# BusPirate-v5.net
KiCad netlist of a schematic drawn in EAGLE
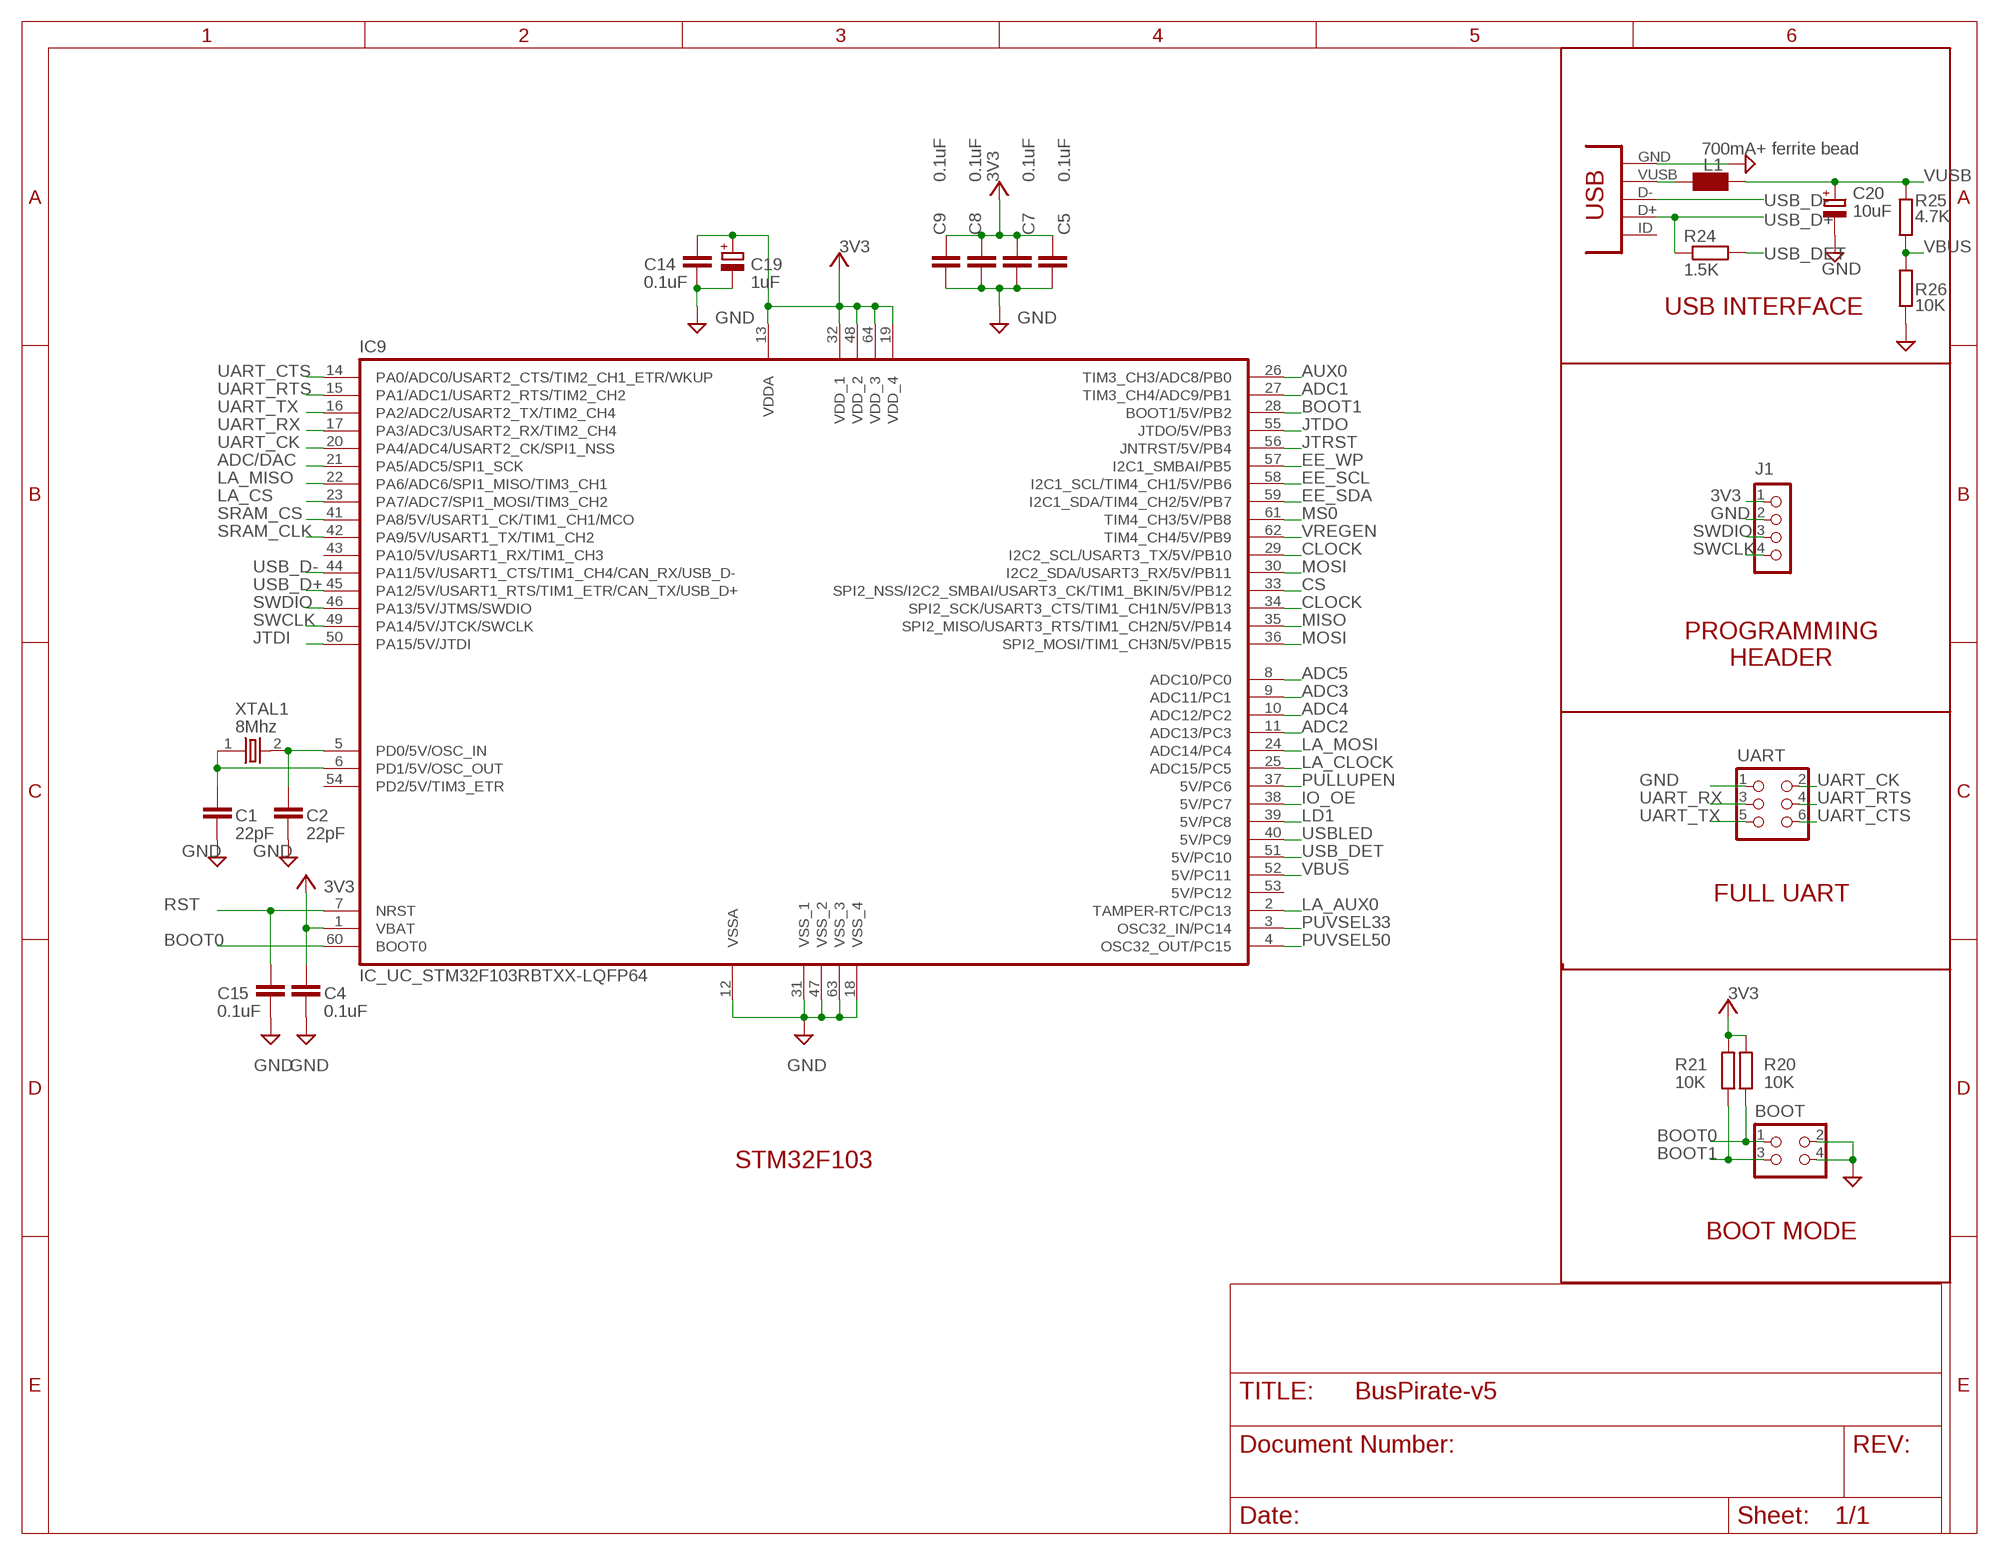
[diagram p0: schematic, sheet 1, part 1 of 2]
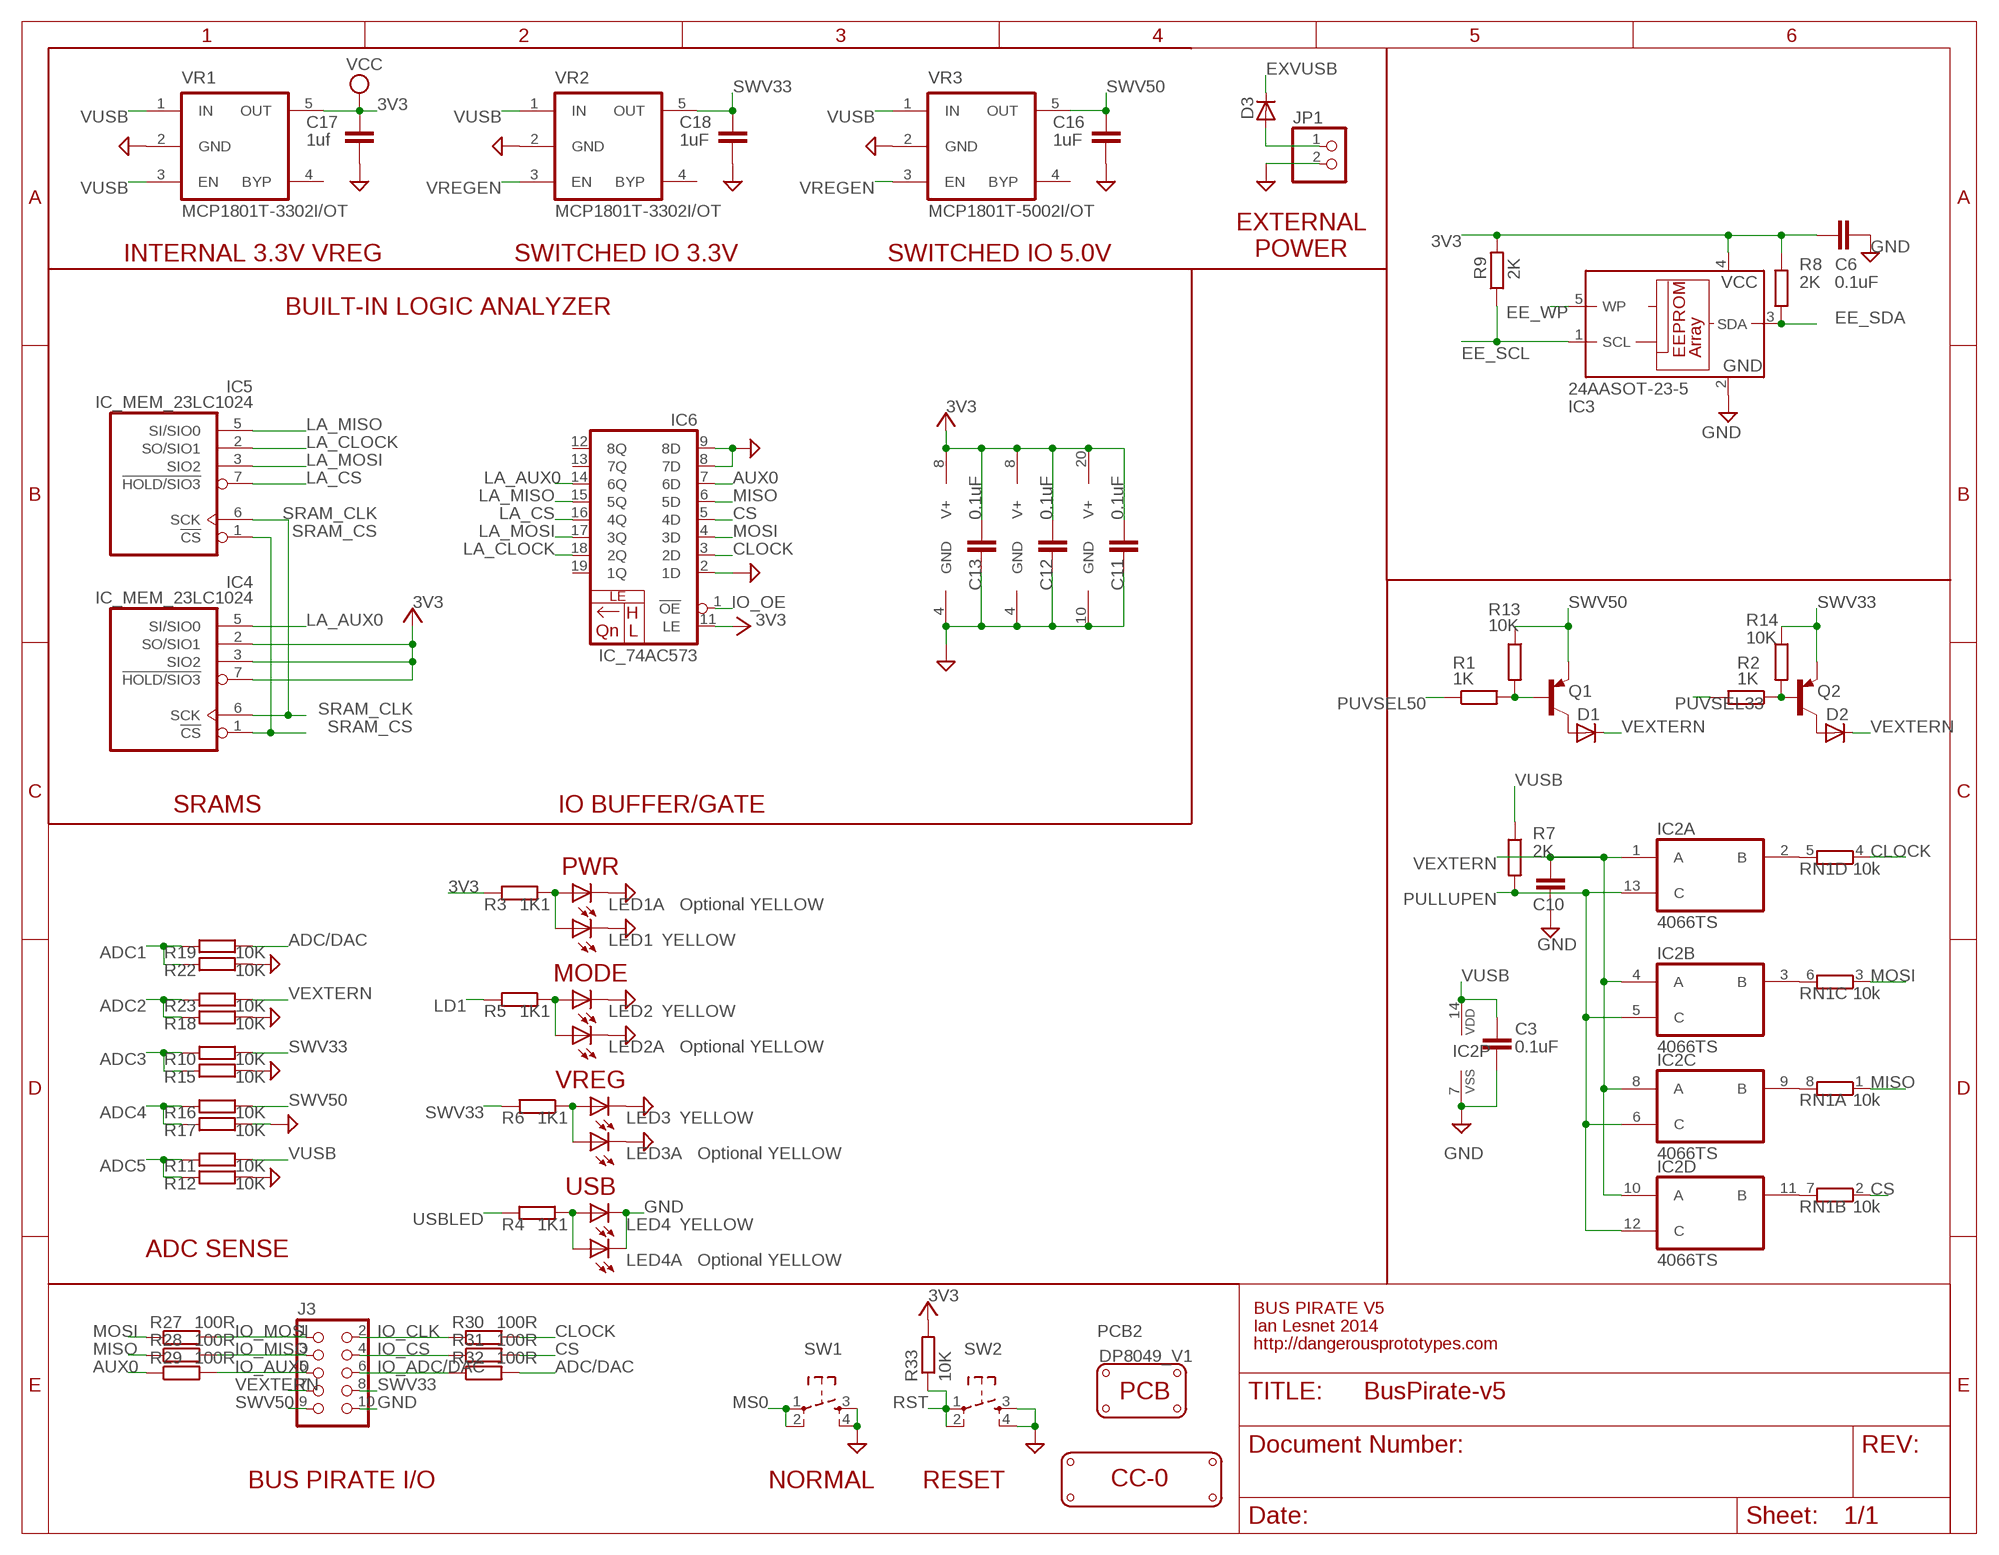
[diagram p1: schematic, sheet 1, part 2 of 2]

(export (version "E")
  (design (tool "Eeschema 10.0.6"))
  (components
    (comp (ref "BOOT")
      (value "CON_HEADER_2X02-PTH")
      (footprint "eagle-import:M2X2")
      (libsource (lib "eagle-import") (part "CON_HEADER_2X02-PTH"))
    )
    (comp (ref "C1")
      (value "22pF")
      (footprint "eagle-import:C0603")
      (libsource (lib "eagle-import") (part "C-EUC0603"))
    )
    (comp (ref "C2")
      (value "22pF")
      (footprint "eagle-import:C0603")
      (libsource (lib "eagle-import") (part "C-EUC0603"))
    )
    (comp (ref "C3")
      (value "0.1uF")
      (footprint "eagle-import:C0603")
      (libsource (lib "eagle-import") (part "C-EUC0603"))
    )
    (comp (ref "C4")
      (value "0.1uF")
      (footprint "eagle-import:C0603")
      (libsource (lib "eagle-import") (part "C-EUC0603"))
    )
    (comp (ref "C5")
      (value "0.1uF")
      (footprint "eagle-import:C0603")
      (libsource (lib "eagle-import") (part "C-EUC0603"))
    )
    (comp (ref "C6")
      (value "0.1uF")
      (footprint "eagle-import:C0603")
      (libsource (lib "eagle-import") (part "C-EUC0603"))
    )
    (comp (ref "C7")
      (value "0.1uF")
      (footprint "eagle-import:C0603")
      (libsource (lib "eagle-import") (part "C-EUC0603"))
    )
    (comp (ref "C8")
      (value "0.1uF")
      (footprint "eagle-import:C0603")
      (libsource (lib "eagle-import") (part "C-EUC0603"))
    )
    (comp (ref "C9")
      (value "0.1uF")
      (footprint "eagle-import:C0603")
      (libsource (lib "eagle-import") (part "C-EUC0603"))
    )
    (comp (ref "C10")
      (value "0.1uF")
      (footprint "eagle-import:C0603")
      (libsource (lib "eagle-import") (part "C-EUC0603"))
    )
    (comp (ref "C11")
      (value "0.1uF")
      (footprint "eagle-import:C0603")
      (libsource (lib "eagle-import") (part "C-EUC0603"))
    )
    (comp (ref "C12")
      (value "0.1uF")
      (footprint "eagle-import:C0603")
      (libsource (lib "eagle-import") (part "C-EUC0603"))
    )
    (comp (ref "C13")
      (value "0.1uF")
      (footprint "eagle-import:C0603")
      (libsource (lib "eagle-import") (part "C-EUC0603"))
    )
    (comp (ref "C14")
      (value "0.1uF")
      (footprint "eagle-import:C0603")
      (libsource (lib "eagle-import") (part "C-EUC0603"))
    )
    (comp (ref "C15")
      (value "0.1uF")
      (footprint "eagle-import:C0603")
      (libsource (lib "eagle-import") (part "C-EUC0603"))
    )
    (comp (ref "C16")
      (value "1uF")
      (footprint "eagle-import:C0603")
      (libsource (lib "eagle-import") (part "C-EUC0603"))
    )
    (comp (ref "C17")
      (value "1uf")
      (footprint "eagle-import:C0603")
      (libsource (lib "eagle-import") (part "C-EUC0603"))
    )
    (comp (ref "C18")
      (value "1uF")
      (footprint "eagle-import:C0603")
      (libsource (lib "eagle-import") (part "C-EUC0603"))
    )
    (comp (ref "C19")
      (value "1uF")
      (footprint "eagle-import:SMC_A")
      (libsource (lib "eagle-import") (part "CPOL-EUSMCA"))
    )
    (comp (ref "C20")
      (value "10uF")
      (footprint "eagle-import:SMC_A")
      (libsource (lib "eagle-import") (part "CPOL-EUSMCA"))
    )
    (comp (ref "D1")
      (value "MBR0520LT")
      (footprint "eagle-import:SOD123")
      (libsource (lib "eagle-import") (part "MBR0520LT"))
    )
    (comp (ref "D2")
      (value "MBR0520LT")
      (footprint "eagle-import:SOD123")
      (libsource (lib "eagle-import") (part "MBR0520LT"))
    )
    (comp (ref "D3")
      (value "MBR0520LT")
      (footprint "eagle-import:SOD123")
      (libsource (lib "eagle-import") (part "MBR0520LT"))
    )
    (comp (ref "IC2")
      (value "4066TS")
      (footprint "eagle-import:40XX_TSSOP14")
      (libsource (lib "eagle-import") (part "4066TS"))
    )
    (comp (ref "IC3")
      (value "24AASOT-23-5")
      (footprint "eagle-import:SOT-23-5@1")
      (libsource (lib "eagle-import") (part "24AA"))
    )
    (comp (ref "IC4")
      (value "IC_MEM_23LC1024")
      (footprint "eagle-import:SOIC-8")
      (libsource (lib "eagle-import") (part "IC_MEM_23LC1024"))
    )
    (comp (ref "IC5")
      (value "IC_MEM_23LC1024")
      (footprint "eagle-import:SOIC-8")
      (libsource (lib "eagle-import") (part "IC_MEM_23LC1024"))
    )
    (comp (ref "IC6")
      (value "IC_74AC573")
      (footprint "eagle-import:TSSOP-20")
      (libsource (lib "eagle-import") (part "IC_74AC573-TSSOP-20"))
    )
    (comp (ref "IC9")
      (value "IC_UC_STM32F103RBTXX-LQFP64")
      (footprint "eagle-import:LQFP64")
      (libsource (lib "eagle-import") (part "IC_UC_STM32F103RBTXX-LQFP64"))
    )
    (comp (ref "J1")
      (value "CON_HEADER_1X04")
      (footprint "eagle-import:M1X4")
      (libsource (lib "eagle-import") (part "CON_HEADER_1X04"))
    )
    (comp (ref "J3")
      (value "CON_HEADER_2X05-PTH+SHROUDED_A")
      (footprint "eagle-import:PINSHRD_PTH_2X05")
      (libsource (lib "eagle-import") (part "CON_HEADER_2X05-PTH+SHROUDED_A"))
    )
    (comp (ref "JP1")
      (value "PINHD-1X02_2.54-S")
      (footprint "eagle-import:1X02-S")
      (libsource (lib "eagle-import") (part "PINHD-1X02_2.54-S"))
    )
    (comp (ref "L1")
      (value "700mA+ ferrite bead")
      (footprint "eagle-import:WE-KI_0805_B")
      (libsource (lib "eagle-import") (part "WE-KIL_0805"))
    )
    (comp (ref "LED1")
      (value "YELLOW")
      (footprint "eagle-import:LED-603")
      (libsource (lib "eagle-import") (part "LED-0603"))
    )
    (comp (ref "LED1A")
      (value "Optional YELLOW")
      (footprint "eagle-import:LED-603")
      (libsource (lib "eagle-import") (part "LED-0603"))
    )
    (comp (ref "LED2")
      (value "YELLOW")
      (footprint "eagle-import:LED-603")
      (libsource (lib "eagle-import") (part "LED-0603"))
    )
    (comp (ref "LED2A")
      (value "Optional YELLOW")
      (footprint "eagle-import:LED-603")
      (libsource (lib "eagle-import") (part "LED-0603"))
    )
    (comp (ref "LED3")
      (value "YELLOW")
      (footprint "eagle-import:LED-603")
      (libsource (lib "eagle-import") (part "LED-0603"))
    )
    (comp (ref "LED3A")
      (value "Optional YELLOW")
      (footprint "eagle-import:LED-603")
      (libsource (lib "eagle-import") (part "LED-0603"))
    )
    (comp (ref "LED4")
      (value "YELLOW")
      (footprint "eagle-import:LED-603")
      (libsource (lib "eagle-import") (part "LED-0603"))
    )
    (comp (ref "LED4A")
      (value "Optional YELLOW")
      (footprint "eagle-import:LED-603")
      (libsource (lib "eagle-import") (part "LED-0603"))
    )
    (comp (ref "LOGO1")
      (value "LOGO_CC-0")
      (footprint "eagle-import:LOGO_CC-0")
      (libsource (lib "eagle-import") (part "LOGO_CC-0"))
    )
    (comp (ref "PCB2")
      (value "PCB_DP_RECTANGLE-80X49")
      (footprint "eagle-import:DP8049_V1")
      (fields (field (name "PCB_SIZE") "DP8049_V1"))
      (libsource (lib "eagle-import") (part "PCB_DP_RECTANGLE-80X49"))
    )
    (comp (ref "Q1")
      (value "MMBTA56-SOT23")
      (footprint "eagle-import:SOT23")
      (libsource (lib "eagle-import") (part "-?SOT23MMBTA56"))
    )
    (comp (ref "Q2")
      (value "MMBTA56-SOT23")
      (footprint "eagle-import:SOT23")
      (libsource (lib "eagle-import") (part "-?SOT23MMBTA56"))
    )
    (comp (ref "R1")
      (value "1K")
      (footprint "eagle-import:R603")
      (libsource (lib "eagle-import") (part "dp_devices.v6_RESISTOR-0603"))
    )
    (comp (ref "R2")
      (value "1K")
      (footprint "eagle-import:R0603")
      (libsource (lib "eagle-import") (part "R-EU_R0603"))
    )
    (comp (ref "R3")
      (value "1K1")
      (footprint "eagle-import:R603")
      (libsource (lib "eagle-import") (part "RESISTOR-0603"))
    )
    (comp (ref "R4")
      (value "1K1")
      (footprint "eagle-import:R603")
      (libsource (lib "eagle-import") (part "RESISTOR-0603"))
    )
    (comp (ref "R5")
      (value "1K1")
      (footprint "eagle-import:R603")
      (libsource (lib "eagle-import") (part "RESISTOR-0603"))
    )
    (comp (ref "R6")
      (value "1K1")
      (footprint "eagle-import:R603")
      (libsource (lib "eagle-import") (part "RESISTOR-0603"))
    )
    (comp (ref "R7")
      (value "2K")
      (footprint "eagle-import:R0603")
      (libsource (lib "eagle-import") (part "R-EU_R0603"))
    )
    (comp (ref "R8")
      (value "2K")
      (footprint "eagle-import:R0603")
      (libsource (lib "eagle-import") (part "R-EU_R0603"))
    )
    (comp (ref "R9")
      (value "2K")
      (footprint "eagle-import:R0603")
      (libsource (lib "eagle-import") (part "R-EU_R0603"))
    )
    (comp (ref "R10")
      (value "10K")
      (footprint "eagle-import:R0603")
      (libsource (lib "eagle-import") (part "resistor_R-EU_R0603"))
    )
    (comp (ref "R11")
      (value "10K")
      (footprint "eagle-import:R0603")
      (libsource (lib "eagle-import") (part "resistor_R-EU_R0603"))
    )
    (comp (ref "R12")
      (value "10K")
      (footprint "eagle-import:R0603")
      (libsource (lib "eagle-import") (part "resistor_R-EU_R0603"))
    )
    (comp (ref "R13")
      (value "10K")
      (footprint "eagle-import:R603")
      (libsource (lib "eagle-import") (part "RESISTOR-0603"))
    )
    (comp (ref "R14")
      (value "10K")
      (footprint "eagle-import:R0603")
      (libsource (lib "eagle-import") (part "R-EU_R0603"))
    )
    (comp (ref "R15")
      (value "10K")
      (footprint "eagle-import:R0603")
      (libsource (lib "eagle-import") (part "resistor_R-EU_R0603"))
    )
    (comp (ref "R16")
      (value "10K")
      (footprint "eagle-import:R0603")
      (libsource (lib "eagle-import") (part "resistor_R-EU_R0603"))
    )
    (comp (ref "R17")
      (value "10K")
      (footprint "eagle-import:R0603")
      (libsource (lib "eagle-import") (part "resistor_R-EU_R0603"))
    )
    (comp (ref "R18")
      (value "10K")
      (footprint "eagle-import:R0603")
      (libsource (lib "eagle-import") (part "resistor_R-EU_R0603"))
    )
    (comp (ref "R19")
      (value "10K")
      (footprint "eagle-import:R0603")
      (libsource (lib "eagle-import") (part "resistor_R-EU_R0603"))
    )
    (comp (ref "R20")
      (value "10K")
      (footprint "eagle-import:R0603")
      (libsource (lib "eagle-import") (part "R-EU_R0603"))
    )
    (comp (ref "R21")
      (value "10K")
      (footprint "eagle-import:R0603")
      (libsource (lib "eagle-import") (part "R-EU_R0603"))
    )
    (comp (ref "R22")
      (value "10K")
      (footprint "eagle-import:R0603")
      (libsource (lib "eagle-import") (part "resistor_R-EU_R0603"))
    )
    (comp (ref "R23")
      (value "10K")
      (footprint "eagle-import:R0603")
      (libsource (lib "eagle-import") (part "resistor_R-EU_R0603"))
    )
    (comp (ref "R24")
      (value "1.5K")
      (footprint "eagle-import:R603")
      (libsource (lib "eagle-import") (part "dp_devices.v6_RESISTOR-0603"))
    )
    (comp (ref "R25")
      (value "4.7K")
      (footprint "eagle-import:R603")
      (libsource (lib "eagle-import") (part "dp_devices.v6_RESISTOR-0603"))
    )
    (comp (ref "R26")
      (value "10K")
      (footprint "eagle-import:R603")
      (libsource (lib "eagle-import") (part "dp_devices.v6_RESISTOR-0603"))
    )
    (comp (ref "R27")
      (value "100R")
      (footprint "eagle-import:R603")
      (libsource (lib "eagle-import") (part "dp_devices.v6_RESISTOR-0603"))
    )
    (comp (ref "R28")
      (value "100R")
      (footprint "eagle-import:R603")
      (libsource (lib "eagle-import") (part "dp_devices.v6_RESISTOR-0603"))
    )
    (comp (ref "R29")
      (value "100R")
      (footprint "eagle-import:R603")
      (libsource (lib "eagle-import") (part "dp_devices.v6_RESISTOR-0603"))
    )
    (comp (ref "R30")
      (value "100R")
      (footprint "eagle-import:R603")
      (libsource (lib "eagle-import") (part "dp_devices.v6_RESISTOR-0603"))
    )
    (comp (ref "R31")
      (value "100R")
      (footprint "eagle-import:R603")
      (libsource (lib "eagle-import") (part "dp_devices.v6_RESISTOR-0603"))
    )
    (comp (ref "R32")
      (value "100R")
      (footprint "eagle-import:R603")
      (libsource (lib "eagle-import") (part "dp_devices.v6_RESISTOR-0603"))
    )
    (comp (ref "R33")
      (value "10K")
      (footprint "eagle-import:R603")
      (libsource (lib "eagle-import") (part "dp_devices.v6_RESISTOR-0603"))
    )
    (comp (ref "RN1")
      (value "10k")
      (footprint "eagle-import:RN8P-4R-CRA06S")
      (libsource (lib "eagle-import") (part "RNETWORK"))
    )
    (comp (ref "SW1")
      (value "SW_TACT_4P")
      (footprint "eagle-import:SW_TACT_SMALL")
      (libsource (lib "eagle-import") (part "SW_TACT_4P"))
    )
    (comp (ref "SW2")
      (value "SW_TACT_4P")
      (footprint "eagle-import:SW_TACT_SMALL")
      (libsource (lib "eagle-import") (part "SW_TACT_4P"))
    )
    (comp (ref "UART")
      (value "CON_HEADER_2X03-PTH")
      (footprint "eagle-import:M2X3")
      (libsource (lib "eagle-import") (part "CON_HEADER_2X03-PTH"))
    )
    (comp (ref "USB")
      (value "USB mini-b")
      (footprint "eagle-import:CONN_USB_MINI-B")
      (libsource (lib "eagle-import") (part "CON-USB-MINI-BUSB1"))
    )
    (comp (ref "VR1")
      (value "MCP1801T-3302I/OT")
      (footprint "eagle-import:SOT-23-5@1")
      (libsource (lib "eagle-import") (part "MIC5205"))
    )
    (comp (ref "VR2")
      (value "MCP1801T-3302I/OT")
      (footprint "eagle-import:SOT-23-5@1")
      (libsource (lib "eagle-import") (part "MIC5205"))
    )
    (comp (ref "VR3")
      (value "MCP1801T-5002I/OT")
      (footprint "eagle-import:SOT-23-5@1")
      (libsource (lib "eagle-import") (part "MIC5205"))
    )
    (comp (ref "XTAL1")
      (value "8Mhz")
      (footprint "eagle-import:XTAL_4X6")
      (libsource (lib "eagle-import") (part "OSC-XTAL-12M"))
    )
  )
  (nets
    (net (code "1") (name "/ADC1") (class "Default")
      (node (ref "IC9") (pin "27") (pinfunction "TIM3_CH4/ADC9/PB1_27") (pintype "bidirectional"))
      (node (ref "R19") (pin "2") (pinfunction "2_2") (pintype "passive"))
      (node (ref "R22") (pin "2") (pinfunction "2_2") (pintype "passive"))
    )
    (net (code "2") (name "/ADC2") (class "Default")
      (node (ref "IC9") (pin "11") (pinfunction "ADC13/PC3_11") (pintype "bidirectional"))
      (node (ref "R18") (pin "2") (pinfunction "2_2") (pintype "passive"))
      (node (ref "R23") (pin "2") (pinfunction "2_2") (pintype "passive"))
    )
    (net (code "3") (name "/ADC3") (class "Default")
      (node (ref "IC9") (pin "9") (pinfunction "ADC11/PC1_9") (pintype "bidirectional"))
      (node (ref "R10") (pin "2") (pinfunction "2_2") (pintype "passive"))
      (node (ref "R15") (pin "2") (pinfunction "2_2") (pintype "passive"))
    )
    (net (code "4") (name "/ADC4") (class "Default")
      (node (ref "IC9") (pin "10") (pinfunction "ADC12/PC2_10") (pintype "bidirectional"))
      (node (ref "R16") (pin "2") (pinfunction "2_2") (pintype "passive"))
      (node (ref "R17") (pin "2") (pinfunction "2_2") (pintype "passive"))
    )
    (net (code "5") (name "/ADC5") (class "Default")
      (node (ref "IC9") (pin "8") (pinfunction "ADC10/PC0_8") (pintype "bidirectional"))
      (node (ref "R11") (pin "2") (pinfunction "2_2") (pintype "passive"))
      (node (ref "R12") (pin "2") (pinfunction "2_2") (pintype "passive"))
    )
    (net (code "6") (name "/ADC{slash}DAC") (class "Default")
      (node (ref "IC9") (pin "21") (pinfunction "PA5/ADC5/SPI1_SCK_21") (pintype "bidirectional"))
      (node (ref "R19") (pin "1") (pinfunction "1_1") (pintype "passive"))
      (node (ref "R32") (pin "2") (pinfunction "2_2") (pintype "passive"))
    )
    (net (code "7") (name "/AUX0") (class "Default")
      (node (ref "IC6") (pin "7") (pinfunction "6D_7") (pintype "bidirectional"))
      (node (ref "IC9") (pin "26") (pinfunction "TIM3_CH3/ADC8/PB0_26") (pintype "bidirectional"))
      (node (ref "R29") (pin "1") (pinfunction "1_1") (pintype "passive"))
    )
    (net (code "8") (name "/BOOT0") (class "Default")
      (node (ref "BOOT") (pin "1") (pinfunction "1_1") (pintype "passive"))
      (node (ref "IC9") (pin "60") (pinfunction "BOOT0_60") (pintype "input"))
      (node (ref "R20") (pin "1") (pinfunction "1_1") (pintype "passive"))
    )
    (net (code "9") (name "/BOOT1") (class "Default")
      (node (ref "BOOT") (pin "3") (pinfunction "3_3") (pintype "passive"))
      (node (ref "IC9") (pin "28") (pinfunction "BOOT1/5V/PB2_28") (pintype "bidirectional"))
      (node (ref "R21") (pin "1") (pinfunction "1_1") (pintype "passive"))
    )
    (net (code "10") (name "/CLOCK") (class "Default")
      (node (ref "IC6") (pin "3") (pinfunction "2D_3") (pintype "bidirectional"))
      (node (ref "IC9") (pin "29") (pinfunction "I2C2_SCL/USART3_TX/5V/PB10_29") (pintype "bidirectional"))
      (node (ref "IC9") (pin "34") (pinfunction "SPI2_SCK/USART3_CTS/TIM1_CH1N/5V/PB13_34") (pintype "bidirectional"))
      (node (ref "R30") (pin "2") (pinfunction "2_2") (pintype "passive"))
      (node (ref "RN1") (pin "4") (pinfunction "1_4") (pintype "passive"))
    )
    (net (code "11") (name "/CS") (class "Default")
      (node (ref "IC6") (pin "5") (pinfunction "4D_5") (pintype "bidirectional"))
      (node (ref "IC9") (pin "33") (pinfunction "SPI2_NSS/I2C2_SMBAI/USART3_CK/TIM1_BKIN/5V/PB12_33") (pintype "bidirectional"))
      (node (ref "R31") (pin "2") (pinfunction "2_2") (pintype "passive"))
      (node (ref "RN1") (pin "2") (pinfunction "1_2") (pintype "passive"))
    )
    (net (code "12") (name "/EE_SCL") (class "Default")
      (node (ref "IC3") (pin "1") (pinfunction "SCL_1") (pintype "input"))
      (node (ref "IC9") (pin "58") (pinfunction "I2C1_SCL/TIM4_CH1/5V/PB6_58") (pintype "bidirectional"))
      (node (ref "R9") (pin "1") (pinfunction "1_1") (pintype "passive"))
    )
    (net (code "13") (name "/EE_SDA") (class "Default")
      (node (ref "IC3") (pin "3") (pinfunction "SDA_3") (pintype "bidirectional"))
      (node (ref "IC9") (pin "59") (pinfunction "I2C1_SDA/TIM4_CH2/5V/PB7_59") (pintype "bidirectional"))
      (node (ref "R8") (pin "1") (pinfunction "1_1") (pintype "passive"))
    )
    (net (code "14") (name "/EE_WP") (class "Default")
      (node (ref "IC3") (pin "5") (pinfunction "WP_5") (pintype "input"))
      (node (ref "IC9") (pin "57") (pinfunction "I2C1_SMBAI/PB5_57") (pintype "bidirectional"))
    )
    (net (code "15") (name "/EXVUSB") (class "Default")
      (node (ref "D3") (pin "C") (pinfunction "C_C") (pintype "passive"))
      (node (ref "L1") (pin "2") (pinfunction "1_2") (pintype "passive"))
      (node (ref "USB") (pin "VUSB") (pinfunction "VUSB_VUSB") (pintype "bidirectional"))
    )
    (net (code "16") (name "/IO_ADC{slash}DAC") (class "Default")
      (node (ref "J3") (pin "6") (pinfunction "6_6") (pintype "passive"))
      (node (ref "R32") (pin "1") (pinfunction "1_1") (pintype "passive"))
    )
    (net (code "17") (name "/IO_AUX0") (class "Default")
      (node (ref "J3") (pin "5") (pinfunction "5_5") (pintype "passive"))
      (node (ref "R29") (pin "2") (pinfunction "2_2") (pintype "passive"))
    )
    (net (code "18") (name "/IO_CLK") (class "Default")
      (node (ref "J3") (pin "2") (pinfunction "2_2") (pintype "passive"))
      (node (ref "R30") (pin "1") (pinfunction "1_1") (pintype "passive"))
    )
    (net (code "19") (name "/IO_CS") (class "Default")
      (node (ref "J3") (pin "4") (pinfunction "4_4") (pintype "passive"))
      (node (ref "R31") (pin "1") (pinfunction "1_1") (pintype "passive"))
    )
    (net (code "20") (name "/IO_MISO") (class "Default")
      (node (ref "J3") (pin "3") (pinfunction "3_3") (pintype "passive"))
      (node (ref "R28") (pin "2") (pinfunction "2_2") (pintype "passive"))
    )
    (net (code "21") (name "/IO_MOSI") (class "Default")
      (node (ref "J3") (pin "1") (pinfunction "1_1") (pintype "passive"))
      (node (ref "R27") (pin "2") (pinfunction "2_2") (pintype "passive"))
    )
    (net (code "22") (name "/IO_OE") (class "Default")
      (node (ref "IC6") (pin "1") (pinfunction "~{OE}_1") (pintype "input"))
      (node (ref "IC9") (pin "38") (pinfunction "5V/PC7_38") (pintype "bidirectional"))
    )
    (net (code "23") (name "/JTDI") (class "Default")
      (node (ref "IC9") (pin "50") (pinfunction "PA15/5V/JTDI_50") (pintype "bidirectional"))
    )
    (net (code "24") (name "/JTDO") (class "Default")
      (node (ref "IC9") (pin "55") (pinfunction "JTDO/5V/PB3_55") (pintype "bidirectional"))
    )
    (net (code "25") (name "/JTRST") (class "Default")
      (node (ref "IC9") (pin "56") (pinfunction "JNTRST/5V/PB4_56") (pintype "bidirectional"))
    )
    (net (code "26") (name "/LA_AUX0") (class "Default")
      (node (ref "IC4") (pin "5") (pinfunction "SI/SIO0_5") (pintype "bidirectional"))
      (node (ref "IC6") (pin "14") (pinfunction "6Q_14") (pintype "bidirectional"))
      (node (ref "IC9") (pin "2") (pinfunction "TAMPER-RTC/PC13_2") (pintype "bidirectional"))
    )
    (net (code "27") (name "/LA_CLOCK") (class "Default")
      (node (ref "IC5") (pin "2") (pinfunction "SO/SIO1_2") (pintype "bidirectional"))
      (node (ref "IC6") (pin "18") (pinfunction "2Q_18") (pintype "bidirectional"))
      (node (ref "IC9") (pin "25") (pinfunction "ADC15/PC5_25") (pintype "bidirectional"))
    )
    (net (code "28") (name "/LA_CS") (class "Default")
      (node (ref "IC5") (pin "7") (pinfunction "~{HOLD/SIO3}_7") (pintype "input"))
      (node (ref "IC6") (pin "16") (pinfunction "4Q_16") (pintype "bidirectional"))
      (node (ref "IC9") (pin "23") (pinfunction "PA7/ADC7/SPI1_MOSI/TIM3_CH2_23") (pintype "bidirectional"))
    )
    (net (code "29") (name "/LA_MISO") (class "Default")
      (node (ref "IC5") (pin "5") (pinfunction "SI/SIO0_5") (pintype "bidirectional"))
      (node (ref "IC6") (pin "15") (pinfunction "5Q_15") (pintype "bidirectional"))
      (node (ref "IC9") (pin "22") (pinfunction "PA6/ADC6/SPI1_MISO/TIM3_CH1_22") (pintype "bidirectional"))
    )
    (net (code "30") (name "/LA_MOSI") (class "Default")
      (node (ref "IC5") (pin "3") (pinfunction "SIO2_3") (pintype "bidirectional"))
      (node (ref "IC6") (pin "17") (pinfunction "3Q_17") (pintype "bidirectional"))
      (node (ref "IC9") (pin "24") (pinfunction "ADC14/PC4_24") (pintype "bidirectional"))
    )
    (net (code "31") (name "/LD1") (class "Default")
      (node (ref "IC9") (pin "39") (pinfunction "5V/PC8_39") (pintype "bidirectional"))
      (node (ref "R5") (pin "2") (pinfunction "2_2") (pintype "passive"))
    )
    (net (code "32") (name "/MISO") (class "Default")
      (node (ref "IC6") (pin "6") (pinfunction "5D_6") (pintype "bidirectional"))
      (node (ref "IC9") (pin "35") (pinfunction "SPI2_MISO/USART3_RTS/TIM1_CH2N/5V/PB14_35") (pintype "bidirectional"))
      (node (ref "R28") (pin "1") (pinfunction "1_1") (pintype "passive"))
      (node (ref "RN1") (pin "1") (pinfunction "1_1") (pintype "passive"))
    )
    (net (code "33") (name "/MOSI") (class "Default")
      (node (ref "IC6") (pin "4") (pinfunction "3D_4") (pintype "bidirectional"))
      (node (ref "IC9") (pin "30") (pinfunction "I2C2_SDA/USART3_RX/5V/PB11_30") (pintype "bidirectional"))
      (node (ref "IC9") (pin "36") (pinfunction "SPI2_MOSI/TIM1_CH3N/5V/PB15_36") (pintype "bidirectional"))
      (node (ref "R27") (pin "1") (pinfunction "1_1") (pintype "passive"))
      (node (ref "RN1") (pin "3") (pinfunction "1_3") (pintype "passive"))
    )
    (net (code "34") (name "/MS0") (class "Default")
      (node (ref "IC9") (pin "61") (pinfunction "TIM4_CH3/5V/PB8_61") (pintype "bidirectional"))
      (node (ref "SW1") (pin "1") (pinfunction "1_1") (pintype "passive"))
      (node (ref "SW1") (pin "2") (pinfunction "2_2") (pintype "passive"))
    )
    (net (code "35") (name "/PULLUPEN") (class "Default")
      (node (ref "IC2") (pin "12") (pinfunction "C_12") (pintype "input"))
      (node (ref "IC2") (pin "13") (pinfunction "C_13") (pintype "input"))
      (node (ref "IC2") (pin "5") (pinfunction "C_5") (pintype "input"))
      (node (ref "IC2") (pin "6") (pinfunction "C_6") (pintype "input"))
      (node (ref "IC9") (pin "37") (pinfunction "5V/PC6_37") (pintype "bidirectional"))
      (node (ref "R7") (pin "2") (pinfunction "2_2") (pintype "passive"))
    )
    (net (code "36") (name "/PUVSEL33") (class "Default")
      (node (ref "IC9") (pin "3") (pinfunction "OSC32_IN/PC14_3") (pintype "bidirectional"))
      (node (ref "R2") (pin "2") (pinfunction "2_2") (pintype "passive"))
    )
    (net (code "37") (name "/PUVSEL50") (class "Default")
      (node (ref "IC9") (pin "4") (pinfunction "OSC32_OUT/PC15_4") (pintype "bidirectional"))
      (node (ref "R1") (pin "1") (pinfunction "1_1") (pintype "passive"))
    )
    (net (code "38") (name "/RST") (class "Default")
      (node (ref "C15") (pin "2") (pinfunction "2_2") (pintype "passive"))
      (node (ref "IC9") (pin "7") (pinfunction "NRST_7") (pintype "bidirectional"))
      (node (ref "R33") (pin "1") (pinfunction "1_1") (pintype "passive"))
      (node (ref "SW2") (pin "1") (pinfunction "1_1") (pintype "passive"))
      (node (ref "SW2") (pin "2") (pinfunction "2_2") (pintype "passive"))
    )
    (net (code "39") (name "/SRAM_CLK") (class "Default")
      (node (ref "IC4") (pin "6") (pinfunction "SCK_6") (pintype "input"))
      (node (ref "IC5") (pin "6") (pinfunction "SCK_6") (pintype "input"))
      (node (ref "IC9") (pin "42") (pinfunction "PA9/5V/USART1_TX/TIM1_CH2_42") (pintype "bidirectional"))
    )
    (net (code "40") (name "/SRAM_CS") (class "Default")
      (node (ref "IC4") (pin "1") (pinfunction "~{CS}_1") (pintype "input"))
      (node (ref "IC5") (pin "1") (pinfunction "~{CS}_1") (pintype "input"))
      (node (ref "IC9") (pin "41") (pinfunction "PA8/5V/USART1_CK/TIM1_CH1/MCO_41") (pintype "bidirectional"))
    )
    (net (code "41") (name "/SWCLK") (class "Default")
      (node (ref "IC9") (pin "49") (pinfunction "PA14/5V/JTCK/SWCLK_49") (pintype "bidirectional"))
      (node (ref "J1") (pin "4") (pinfunction "4_4") (pintype "bidirectional"))
    )
    (net (code "42") (name "/SWDIO") (class "Default")
      (node (ref "IC9") (pin "46") (pinfunction "PA13/5V/JTMS/SWDIO_46") (pintype "bidirectional"))
      (node (ref "J1") (pin "3") (pinfunction "3_3") (pintype "bidirectional"))
    )
    (net (code "43") (name "/SWV33") (class "Default")
      (node (ref "C18") (pin "1") (pinfunction "1_1") (pintype "passive"))
      (node (ref "J3") (pin "8") (pinfunction "8_8") (pintype "passive"))
      (node (ref "Q2") (pin "2") (pinfunction "E_2") (pintype "passive"))
      (node (ref "R10") (pin "1") (pinfunction "1_1") (pintype "passive"))
      (node (ref "R14") (pin "1") (pinfunction "1_1") (pintype "passive"))
      (node (ref "R6") (pin "2") (pinfunction "2_2") (pintype "passive"))
      (node (ref "VR2") (pin "5") (pinfunction "OUT_5") (pintype "bidirectional"))
    )
    (net (code "44") (name "/SWV50") (class "Default")
      (node (ref "C16") (pin "1") (pinfunction "1_1") (pintype "passive"))
      (node (ref "J3") (pin "9") (pinfunction "9_9") (pintype "passive"))
      (node (ref "Q1") (pin "2") (pinfunction "E_2") (pintype "passive"))
      (node (ref "R13") (pin "1") (pinfunction "1_1") (pintype "passive"))
      (node (ref "R16") (pin "1") (pinfunction "1_1") (pintype "passive"))
      (node (ref "VR3") (pin "5") (pinfunction "OUT_5") (pintype "bidirectional"))
    )
    (net (code "45") (name "/UART_CK") (class "Default")
      (node (ref "IC9") (pin "20") (pinfunction "PA4/ADC4/USART2_CK/SPI1_NSS_20") (pintype "bidirectional"))
      (node (ref "UART") (pin "2") (pinfunction "2_2") (pintype "passive"))
    )
    (net (code "46") (name "/UART_CTS") (class "Default")
      (node (ref "IC9") (pin "14") (pinfunction "PA0/ADC0/USART2_CTS/TIM2_CH1_ETR/WKUP_14") (pintype "bidirectional"))
      (node (ref "UART") (pin "6") (pinfunction "6_6") (pintype "passive"))
    )
    (net (code "47") (name "/UART_RTS") (class "Default")
      (node (ref "IC9") (pin "15") (pinfunction "PA1/ADC1/USART2_RTS/TIM2_CH2_15") (pintype "bidirectional"))
      (node (ref "UART") (pin "4") (pinfunction "4_4") (pintype "passive"))
    )
    (net (code "48") (name "/UART_RX") (class "Default")
      (node (ref "IC9") (pin "17") (pinfunction "PA3/ADC3/USART2_RX/TIM2_CH4_17") (pintype "bidirectional"))
      (node (ref "UART") (pin "3") (pinfunction "3_3") (pintype "passive"))
    )
    (net (code "49") (name "/UART_TX") (class "Default")
      (node (ref "IC9") (pin "16") (pinfunction "PA2/ADC2/USART2_TX/TIM2_CH4_16") (pintype "bidirectional"))
      (node (ref "UART") (pin "5") (pinfunction "5_5") (pintype "passive"))
    )
    (net (code "50") (name "/USBLED") (class "Default")
      (node (ref "IC9") (pin "40") (pinfunction "5V/PC9_40") (pintype "bidirectional"))
      (node (ref "R4") (pin "2") (pinfunction "2_2") (pintype "passive"))
    )
    (net (code "51") (name "/USB_D+") (class "Default")
      (node (ref "IC9") (pin "45") (pinfunction "PA12/5V/USART1_RTS/TIM1_ETR/CAN_TX/USB_D+_45") (pintype "bidirectional"))
      (node (ref "R24") (pin "1") (pinfunction "1_1") (pintype "passive"))
      (node (ref "USB") (pin "D+") (pinfunction "D+_D+") (pintype "bidirectional"))
    )
    (net (code "52") (name "/USB_D-") (class "Default")
      (node (ref "IC9") (pin "44") (pinfunction "PA11/5V/USART1_CTS/TIM1_CH4/CAN_RX/USB_D-_44") (pintype "bidirectional"))
      (node (ref "USB") (pin "D-") (pinfunction "D-_D-") (pintype "bidirectional"))
    )
    (net (code "53") (name "/USB_DET") (class "Default")
      (node (ref "IC9") (pin "51") (pinfunction "5V/PC10_51") (pintype "bidirectional"))
      (node (ref "R24") (pin "2") (pinfunction "2_2") (pintype "passive"))
    )
    (net (code "54") (name "/VBUS") (class "Default")
      (node (ref "IC9") (pin "52") (pinfunction "5V/PC11_52") (pintype "bidirectional"))
      (node (ref "R25") (pin "1") (pinfunction "1_1") (pintype "passive"))
      (node (ref "R26") (pin "2") (pinfunction "2_2") (pintype "passive"))
    )
    (net (code "55") (name "/VEXTERN") (class "Default")
      (node (ref "C10") (pin "1") (pinfunction "1_1") (pintype "passive"))
      (node (ref "D1") (pin "C") (pinfunction "C_C") (pintype "passive"))
      (node (ref "D2") (pin "C") (pinfunction "C_C") (pintype "passive"))
      (node (ref "IC2") (pin "1") (pinfunction "A_1") (pintype "tri_state"))
      (node (ref "IC2") (pin "10") (pinfunction "A_10") (pintype "tri_state"))
      (node (ref "IC2") (pin "4") (pinfunction "A_4") (pintype "tri_state"))
      (node (ref "IC2") (pin "8") (pinfunction "A_8") (pintype "tri_state"))
      (node (ref "J3") (pin "7") (pinfunction "7_7") (pintype "passive"))
      (node (ref "R23") (pin "1") (pinfunction "1_1") (pintype "passive"))
    )
    (net (code "56") (name "/VREGEN") (class "Default")
      (node (ref "IC9") (pin "62") (pinfunction "TIM4_CH4/5V/PB9_62") (pintype "bidirectional"))
      (node (ref "VR2") (pin "3") (pinfunction "EN_3") (pintype "bidirectional"))
      (node (ref "VR3") (pin "3") (pinfunction "EN_3") (pintype "bidirectional"))
    )
    (net (code "57") (name "/VUSB") (class "Default")
      (node (ref "C20") (pin "+") (pinfunction "+_+") (pintype "passive"))
      (node (ref "C3") (pin "1") (pinfunction "1_1") (pintype "passive"))
      (node (ref "IC2") (pin "14") (pinfunction "VDD_14") (pintype "power_in"))
      (node (ref "L1") (pin "1") (pinfunction "2_1") (pintype "passive"))
      (node (ref "R11") (pin "1") (pinfunction "1_1") (pintype "passive"))
      (node (ref "R25") (pin "2") (pinfunction "2_2") (pintype "passive"))
      (node (ref "R7") (pin "1") (pinfunction "1_1") (pintype "passive"))
      (node (ref "VR1") (pin "1") (pinfunction "IN_1") (pintype "bidirectional"))
      (node (ref "VR1") (pin "3") (pinfunction "EN_3") (pintype "bidirectional"))
      (node (ref "VR2") (pin "1") (pinfunction "IN_1") (pintype "bidirectional"))
      (node (ref "VR3") (pin "1") (pinfunction "IN_1") (pintype "bidirectional"))
    )
    (net (code "58") (name "GND") (class "Default")
      (node (ref "BOOT") (pin "2") (pinfunction "2_2") (pintype "passive"))
      (node (ref "BOOT") (pin "4") (pinfunction "4_4") (pintype "passive"))
      (node (ref "C1") (pin "1") (pinfunction "1_1") (pintype "passive"))
      (node (ref "C10") (pin "2") (pinfunction "2_2") (pintype "passive"))
      (node (ref "C11") (pin "2") (pinfunction "2_2") (pintype "passive"))
      (node (ref "C12") (pin "2") (pinfunction "2_2") (pintype "passive"))
      (node (ref "C13") (pin "2") (pinfunction "2_2") (pintype "passive"))
      (node (ref "C14") (pin "1") (pinfunction "1_1") (pintype "passive"))
      (node (ref "C15") (pin "1") (pinfunction "1_1") (pintype "passive"))
      (node (ref "C16") (pin "2") (pinfunction "2_2") (pintype "passive"))
      (node (ref "C17") (pin "2") (pinfunction "2_2") (pintype "passive"))
      (node (ref "C18") (pin "2") (pinfunction "2_2") (pintype "passive"))
      (node (ref "C19") (pin "-") (pinfunction "-_-") (pintype "passive"))
      (node (ref "C2") (pin "1") (pinfunction "1_1") (pintype "passive"))
      (node (ref "C20") (pin "-") (pinfunction "-_-") (pintype "passive"))
      (node (ref "C3") (pin "2") (pinfunction "2_2") (pintype "passive"))
      (node (ref "C4") (pin "1") (pinfunction "1_1") (pintype "passive"))
      (node (ref "C5") (pin "1") (pinfunction "1_1") (pintype "passive"))
      (node (ref "C6") (pin "2") (pinfunction "2_2") (pintype "passive"))
      (node (ref "C7") (pin "1") (pinfunction "1_1") (pintype "passive"))
      (node (ref "C8") (pin "1") (pinfunction "1_1") (pintype "passive"))
      (node (ref "C9") (pin "1") (pinfunction "1_1") (pintype "passive"))
      (node (ref "IC2") (pin "7") (pinfunction "VSS_7") (pintype "power_in"))
      (node (ref "IC3") (pin "2") (pinfunction "GND_2") (pintype "power_in"))
      (node (ref "IC4") (pin "4") (pinfunction "GND_4") (pintype "power_in"))
      (node (ref "IC5") (pin "4") (pinfunction "GND_4") (pintype "power_in"))
      (node (ref "IC6") (pin "10") (pinfunction "GND_10") (pintype "power_in"))
      (node (ref "IC6") (pin "2") (pinfunction "1D_2") (pintype "bidirectional"))
      (node (ref "IC6") (pin "8") (pinfunction "7D_8") (pintype "bidirectional"))
      (node (ref "IC6") (pin "9") (pinfunction "8D_9") (pintype "bidirectional"))
      (node (ref "IC9") (pin "12") (pinfunction "VSSA_12") (pintype "power_in"))
      (node (ref "IC9") (pin "18") (pinfunction "VSS_4_18") (pintype "power_in"))
      (node (ref "IC9") (pin "31") (pinfunction "VSS_1_31") (pintype "power_in"))
      (node (ref "IC9") (pin "47") (pinfunction "VSS_2_47") (pintype "power_in"))
      (node (ref "IC9") (pin "63") (pinfunction "VSS_3_63") (pintype "power_in"))
      (node (ref "J1") (pin "2") (pinfunction "2_2") (pintype "bidirectional"))
      (node (ref "J3") (pin "10") (pinfunction "10_10") (pintype "passive"))
      (node (ref "JP1") (pin "2") (pinfunction "2_2") (pintype "passive"))
      (node (ref "LED1") (pin "C") (pinfunction "C_C") (pintype "passive"))
      (node (ref "LED1A") (pin "C") (pinfunction "C_C") (pintype "passive"))
      (node (ref "LED2") (pin "C") (pinfunction "C_C") (pintype "passive"))
      (node (ref "LED2A") (pin "C") (pinfunction "C_C") (pintype "passive"))
      (node (ref "LED3") (pin "C") (pinfunction "C_C") (pintype "passive"))
      (node (ref "LED3A") (pin "C") (pinfunction "C_C") (pintype "passive"))
      (node (ref "LED4") (pin "C") (pinfunction "C_C") (pintype "passive"))
      (node (ref "LED4A") (pin "C") (pinfunction "C_C") (pintype "passive"))
      (node (ref "R12") (pin "1") (pinfunction "1_1") (pintype "passive"))
      (node (ref "R15") (pin "1") (pinfunction "1_1") (pintype "passive"))
      (node (ref "R17") (pin "1") (pinfunction "1_1") (pintype "passive"))
      (node (ref "R18") (pin "1") (pinfunction "1_1") (pintype "passive"))
      (node (ref "R22") (pin "1") (pinfunction "1_1") (pintype "passive"))
      (node (ref "R26") (pin "1") (pinfunction "1_1") (pintype "passive"))
      (node (ref "SW1") (pin "3") (pinfunction "3_3") (pintype "passive"))
      (node (ref "SW1") (pin "4") (pinfunction "4_4") (pintype "passive"))
      (node (ref "SW2") (pin "3") (pinfunction "3_3") (pintype "passive"))
      (node (ref "SW2") (pin "4") (pinfunction "4_4") (pintype "passive"))
      (node (ref "UART") (pin "1") (pinfunction "1_1") (pintype "passive"))
      (node (ref "USB") (pin "GND") (pinfunction "GND_GND") (pintype "bidirectional"))
      (node (ref "VR1") (pin "2") (pinfunction "GND_2") (pintype "bidirectional"))
      (node (ref "VR2") (pin "2") (pinfunction "GND_2") (pintype "bidirectional"))
      (node (ref "VR3") (pin "2") (pinfunction "GND_2") (pintype "bidirectional"))
    )
    (net (code "59") (name "Net-(D3-PadA)") (class "Default")
      (node (ref "D3") (pin "A") (pinfunction "A_A") (pintype "passive"))
      (node (ref "JP1") (pin "1") (pinfunction "1_1") (pintype "passive"))
    )
    (net (code "60") (name "Net-(IC2A-B)") (class "Default")
      (node (ref "IC2") (pin "2") (pinfunction "B_2") (pintype "tri_state"))
      (node (ref "RN1") (pin "5") (pinfunction "2_5") (pintype "passive"))
    )
    (net (code "61") (name "Net-(IC2B-B)") (class "Default")
      (node (ref "IC2") (pin "3") (pinfunction "B_3") (pintype "tri_state"))
      (node (ref "RN1") (pin "6") (pinfunction "2_6") (pintype "passive"))
    )
    (net (code "62") (name "Net-(IC2C-B)") (class "Default")
      (node (ref "IC2") (pin "9") (pinfunction "B_9") (pintype "tri_state"))
      (node (ref "RN1") (pin "8") (pinfunction "2_8") (pintype "passive"))
    )
    (net (code "63") (name "Net-(IC2D-B)") (class "Default")
      (node (ref "IC2") (pin "11") (pinfunction "B_11") (pintype "tri_state"))
      (node (ref "RN1") (pin "7") (pinfunction "2_7") (pintype "passive"))
    )
    (net (code "64") (name "Net-(IC9-PD0{slash}5V{slash}OSC_IN)") (class "Default")
      (node (ref "C2") (pin "2") (pinfunction "2_2") (pintype "passive"))
      (node (ref "IC9") (pin "5") (pinfunction "PD0/5V/OSC_IN_5") (pintype "input"))
      (node (ref "XTAL1") (pin "2") (pinfunction "2_2") (pintype "passive"))
    )
    (net (code "65") (name "Net-(IC9-PD1{slash}5V{slash}OSC_OUT)") (class "Default")
      (node (ref "C1") (pin "2") (pinfunction "2_2") (pintype "passive"))
      (node (ref "IC9") (pin "6") (pinfunction "PD1/5V/OSC_OUT_6") (pintype "output"))
      (node (ref "XTAL1") (pin "1") (pinfunction "1_1") (pintype "passive"))
    )
    (net (code "66") (name "Net-(LED1-PadA)") (class "Default")
      (node (ref "LED1") (pin "A") (pinfunction "A_A") (pintype "passive"))
      (node (ref "LED1A") (pin "A") (pinfunction "A_A") (pintype "passive"))
      (node (ref "R3") (pin "1") (pinfunction "1_1") (pintype "passive"))
    )
    (net (code "67") (name "Net-(LED2-PadA)") (class "Default")
      (node (ref "LED2") (pin "A") (pinfunction "A_A") (pintype "passive"))
      (node (ref "LED2A") (pin "A") (pinfunction "A_A") (pintype "passive"))
      (node (ref "R5") (pin "1") (pinfunction "1_1") (pintype "passive"))
    )
    (net (code "68") (name "Net-(LED3-PadA)") (class "Default")
      (node (ref "LED3") (pin "A") (pinfunction "A_A") (pintype "passive"))
      (node (ref "LED3A") (pin "A") (pinfunction "A_A") (pintype "passive"))
      (node (ref "R6") (pin "1") (pinfunction "1_1") (pintype "passive"))
    )
    (net (code "69") (name "Net-(LED4-PadA)") (class "Default")
      (node (ref "LED4") (pin "A") (pinfunction "A_A") (pintype "passive"))
      (node (ref "LED4A") (pin "A") (pinfunction "A_A") (pintype "passive"))
      (node (ref "R4") (pin "1") (pinfunction "1_1") (pintype "passive"))
    )
    (net (code "70") (name "Net-(Q1-B)") (class "Default")
      (node (ref "Q1") (pin "1") (pinfunction "B_1") (pintype "passive"))
      (node (ref "R1") (pin "2") (pinfunction "2_2") (pintype "passive"))
      (node (ref "R13") (pin "2") (pinfunction "2_2") (pintype "passive"))
    )
    (net (code "71") (name "Net-(Q1-C)") (class "Default")
      (node (ref "D1") (pin "A") (pinfunction "A_A") (pintype "passive"))
      (node (ref "Q1") (pin "3") (pinfunction "C_3") (pintype "passive"))
    )
    (net (code "72") (name "Net-(Q2-B)") (class "Default")
      (node (ref "Q2") (pin "1") (pinfunction "B_1") (pintype "passive"))
      (node (ref "R14") (pin "2") (pinfunction "2_2") (pintype "passive"))
      (node (ref "R2") (pin "1") (pinfunction "1_1") (pintype "passive"))
    )
    (net (code "73") (name "Net-(Q2-C)") (class "Default")
      (node (ref "D2") (pin "A") (pinfunction "A_A") (pintype "passive"))
      (node (ref "Q2") (pin "3") (pinfunction "C_3") (pintype "passive"))
    )
    (net (code "74") (name "V+") (class "Default")
      (node (ref "C11") (pin "1") (pinfunction "1_1") (pintype "passive"))
      (node (ref "C12") (pin "1") (pinfunction "1_1") (pintype "passive"))
      (node (ref "C13") (pin "1") (pinfunction "1_1") (pintype "passive"))
      (node (ref "C14") (pin "2") (pinfunction "2_2") (pintype "passive"))
      (node (ref "C17") (pin "1") (pinfunction "1_1") (pintype "passive"))
      (node (ref "C19") (pin "+") (pinfunction "+_+") (pintype "passive"))
      (node (ref "C4") (pin "2") (pinfunction "2_2") (pintype "passive"))
      (node (ref "C5") (pin "2") (pinfunction "2_2") (pintype "passive"))
      (node (ref "C6") (pin "1") (pinfunction "1_1") (pintype "passive"))
      (node (ref "C7") (pin "2") (pinfunction "2_2") (pintype "passive"))
      (node (ref "C8") (pin "2") (pinfunction "2_2") (pintype "passive"))
      (node (ref "C9") (pin "2") (pinfunction "2_2") (pintype "passive"))
      (node (ref "IC3") (pin "4") (pinfunction "VCC_4") (pintype "power_in"))
      (node (ref "IC4") (pin "2") (pinfunction "SO/SIO1_2") (pintype "bidirectional"))
      (node (ref "IC4") (pin "3") (pinfunction "SIO2_3") (pintype "bidirectional"))
      (node (ref "IC4") (pin "7") (pinfunction "~{HOLD/SIO3}_7") (pintype "input"))
      (node (ref "IC4") (pin "8") (pinfunction "V+_8") (pintype "power_in"))
      (node (ref "IC5") (pin "8") (pinfunction "V+_8") (pintype "power_in"))
      (node (ref "IC6") (pin "11") (pinfunction "LE_11") (pintype "input"))
      (node (ref "IC6") (pin "20") (pinfunction "V+_20") (pintype "power_in"))
      (node (ref "IC9") (pin "1") (pinfunction "VBAT_1") (pintype "power_in"))
      (node (ref "IC9") (pin "13") (pinfunction "VDDA_13") (pintype "power_in"))
      (node (ref "IC9") (pin "19") (pinfunction "VDD_4_19") (pintype "power_in"))
      (node (ref "IC9") (pin "32") (pinfunction "VDD_1_32") (pintype "power_in"))
      (node (ref "IC9") (pin "48") (pinfunction "VDD_2_48") (pintype "power_in"))
      (node (ref "IC9") (pin "64") (pinfunction "VDD_3_64") (pintype "power_in"))
      (node (ref "J1") (pin "1") (pinfunction "1_1") (pintype "bidirectional"))
      (node (ref "R20") (pin "2") (pinfunction "2_2") (pintype "passive"))
      (node (ref "R21") (pin "2") (pinfunction "2_2") (pintype "passive"))
      (node (ref "R3") (pin "2") (pinfunction "2_2") (pintype "passive"))
      (node (ref "R33") (pin "2") (pinfunction "2_2") (pintype "passive"))
      (node (ref "R8") (pin "2") (pinfunction "2_2") (pintype "passive"))
      (node (ref "R9") (pin "2") (pinfunction "2_2") (pintype "passive"))
      (node (ref "VR1") (pin "5") (pinfunction "OUT_5") (pintype "bidirectional"))
    )
    (net (code "75") (name "unconnected-(IC6A-1Q-Pad19)") (class "Default")
      (node (ref "IC6") (pin "19") (pinfunction "1Q_19") (pintype "bidirectional"))
    )
    (net (code "76") (name "unconnected-(IC6A-7Q-Pad13)") (class "Default")
      (node (ref "IC6") (pin "13") (pinfunction "7Q_13") (pintype "bidirectional"))
    )
    (net (code "77") (name "unconnected-(IC6A-8Q-Pad12)") (class "Default")
      (node (ref "IC6") (pin "12") (pinfunction "8Q_12") (pintype "bidirectional"))
    )
    (net (code "78") (name "unconnected-(IC9-5V{slash}PC12-Pad53)") (class "Default")
      (node (ref "IC9") (pin "53") (pinfunction "5V/PC12_53") (pintype "bidirectional"))
    )
    (net (code "79") (name "unconnected-(IC9-PA10{slash}5V{slash}USART1_RX{slash}TIM1_CH3-Pad43)") (class "Default")
      (node (ref "IC9") (pin "43") (pinfunction "PA10/5V/USART1_RX/TIM1_CH3_43") (pintype "bidirectional"))
    )
    (net (code "80") (name "unconnected-(IC9-PD2{slash}5V{slash}TIM3_ETR-Pad54)") (class "Default")
      (node (ref "IC9") (pin "54") (pinfunction "PD2/5V/TIM3_ETR_54") (pintype "bidirectional"))
    )
    (net (code "81") (name "unconnected-(USBB-USBID-PadID)") (class "Default")
      (node (ref "USB") (pin "ID") (pinfunction "USBID_ID") (pintype "bidirectional"))
    )
    (net (code "82") (name "unconnected-(VR1-BYP-Pad4)") (class "Default")
      (node (ref "VR1") (pin "4") (pinfunction "BYP_4") (pintype "bidirectional"))
    )
    (net (code "83") (name "unconnected-(VR2-BYP-Pad4)") (class "Default")
      (node (ref "VR2") (pin "4") (pinfunction "BYP_4") (pintype "bidirectional"))
    )
    (net (code "84") (name "unconnected-(VR3-BYP-Pad4)") (class "Default")
      (node (ref "VR3") (pin "4") (pinfunction "BYP_4") (pintype "bidirectional"))
    )
  )
)
